# ProPrj_agronet_2025-02-23.net
KiCad netlist of a schematic drawn in EasyEDA Pro
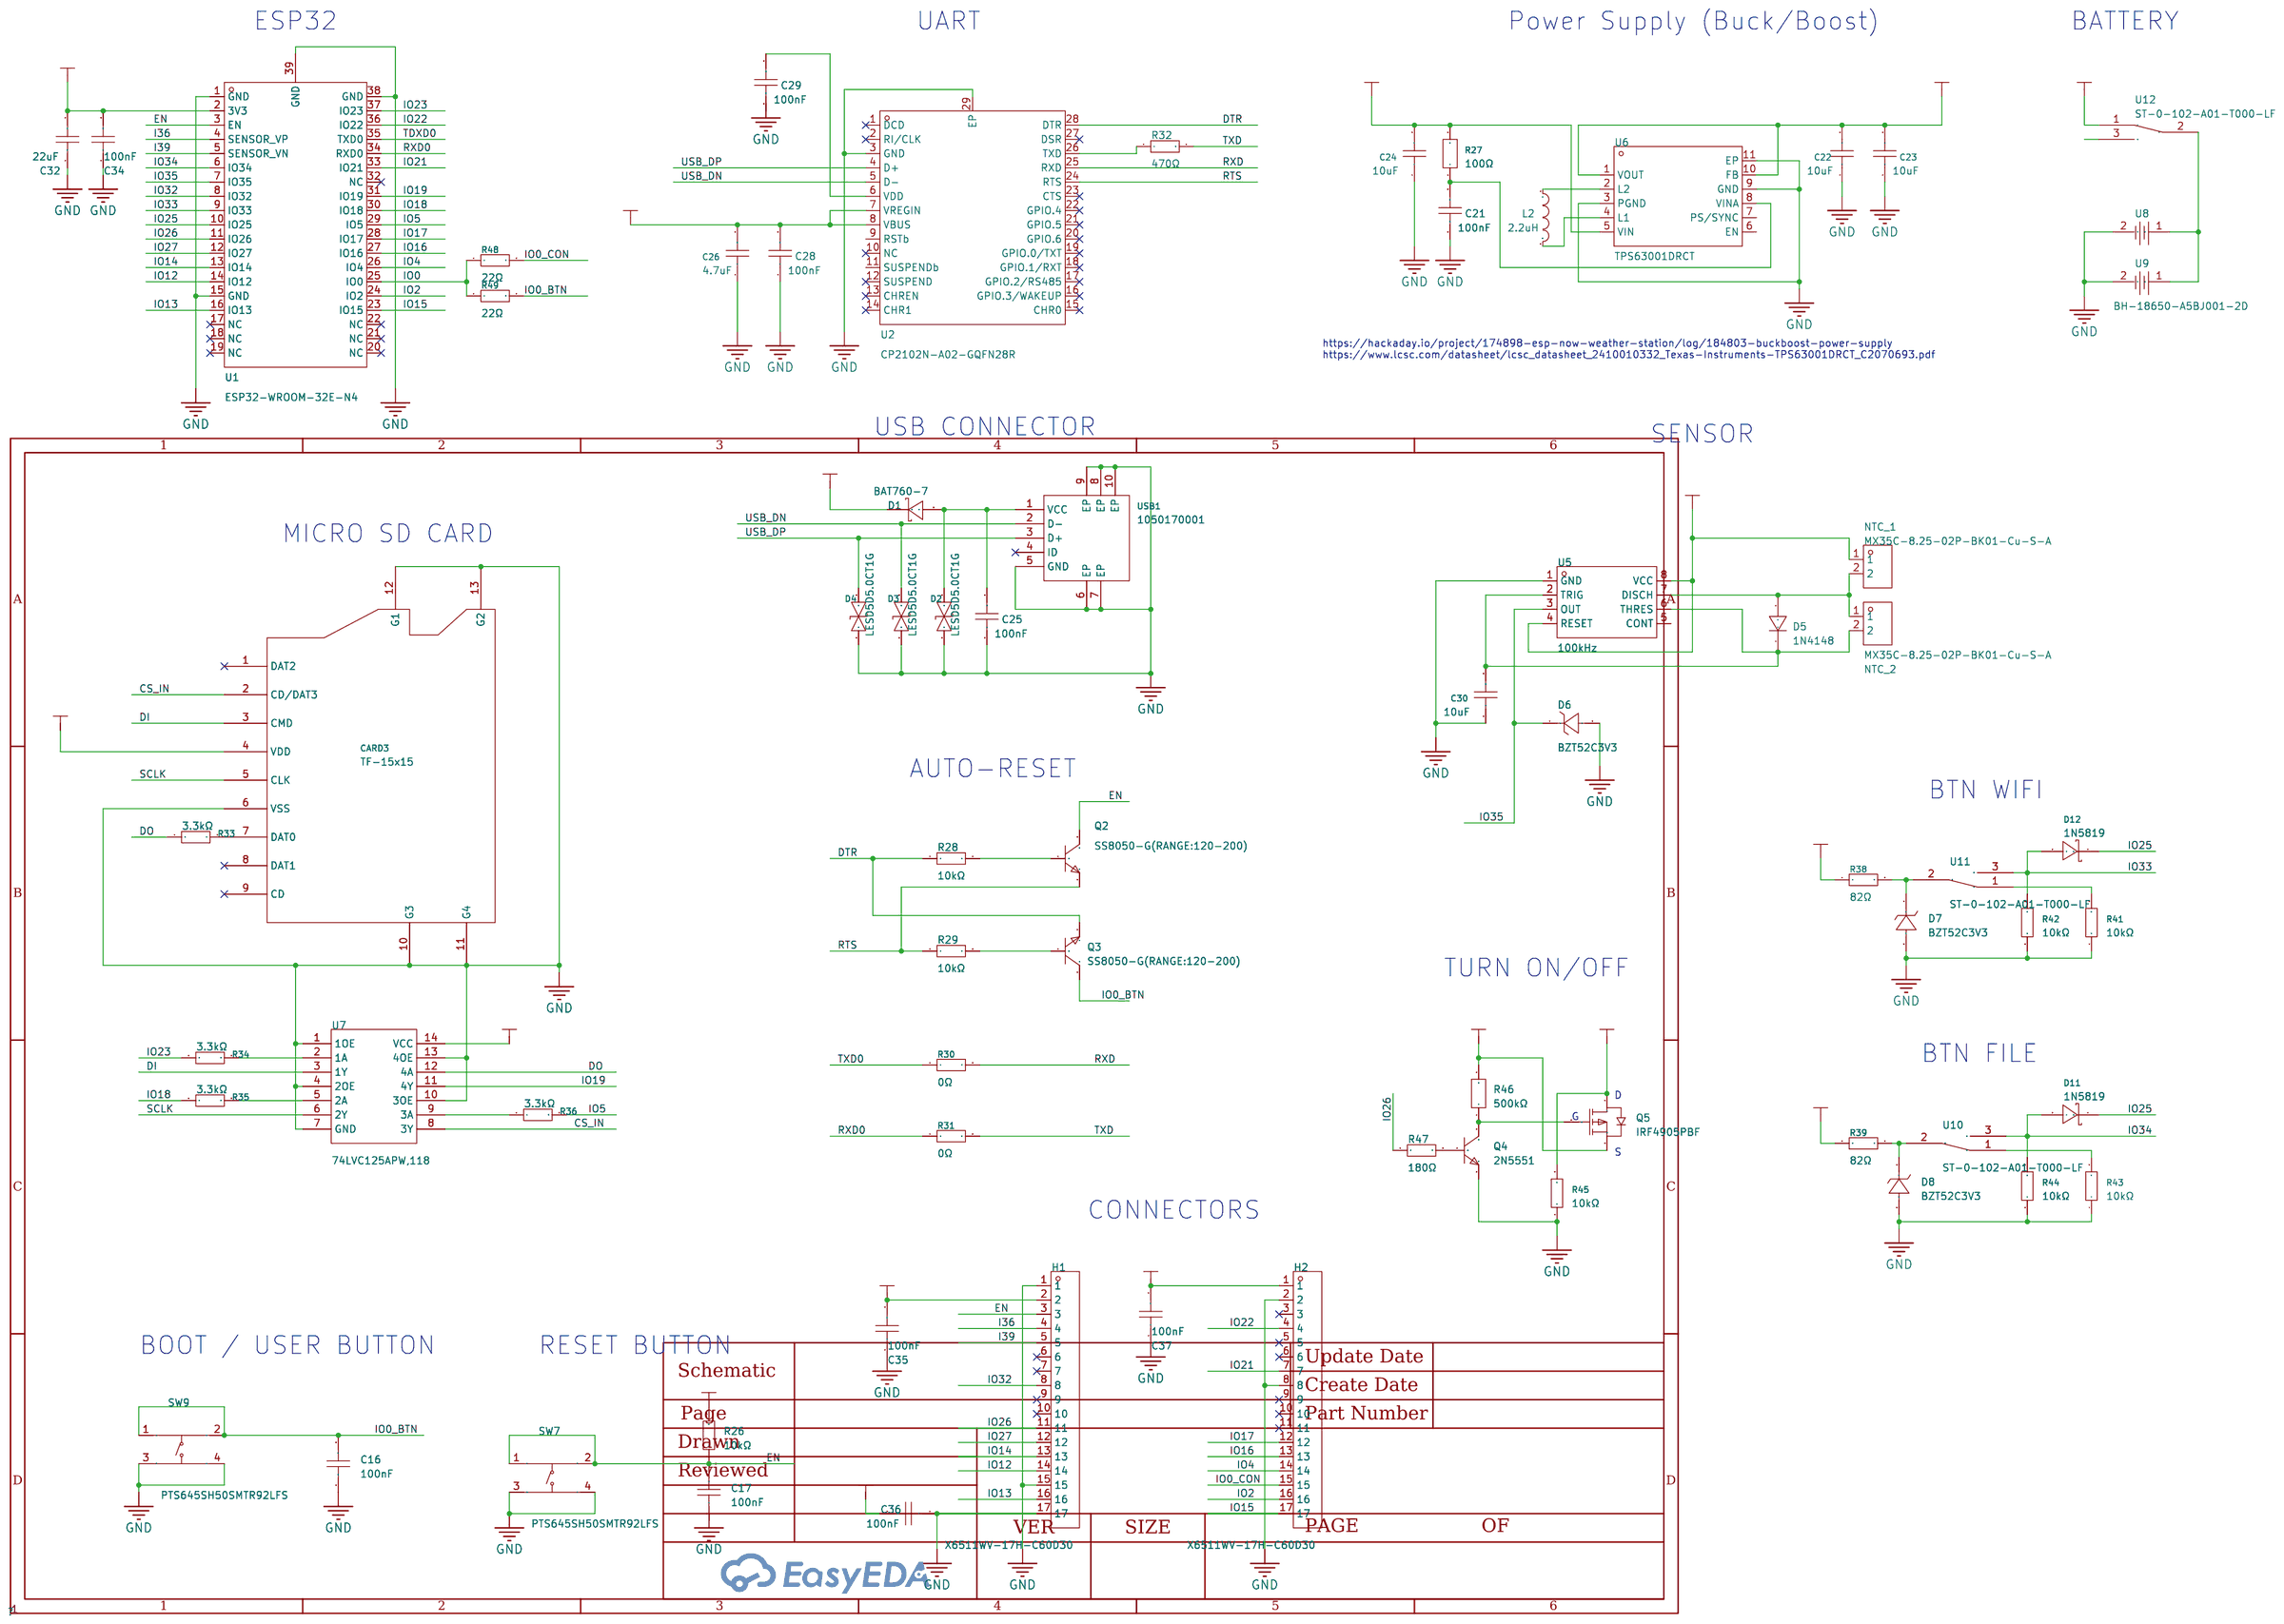
[diagram p0: schematic sheet]

(export (version "E")
  (design (tool "Eeschema 10.0.6"))
  (components
    (comp (ref "C16")
      (value "100nF")
      (footprint "easyedapro:C0402")
      (fields
        (field (name "Manufacturer Part") "CL05B104KO5NNNC")
        (field (name "Manufacturer") "SAMSUNG(三星)")
      )
      (libsource (lib "easyedapro") (part "CL05B104KO5NNNC"))
    )
    (comp (ref "C17")
      (value "100nF")
      (footprint "easyedapro:C0402")
      (fields
        (field (name "Manufacturer Part") "CL05B104KO5NNNC")
        (field (name "Manufacturer") "SAMSUNG(三星)")
      )
      (libsource (lib "easyedapro") (part "CL05B104KO5NNNC"))
    )
    (comp (ref "C21")
      (value "100nF")
      (footprint "easyedapro:C0402")
      (fields
        (field (name "Manufacturer Part") "CL05B104KO5NNNC")
        (field (name "Manufacturer") "SAMSUNG(三星)")
      )
      (libsource (lib "easyedapro") (part "CL05B104KO5NNNC"))
    )
    (comp (ref "C22")
      (value "10uF")
      (footprint "easyedapro:C0603")
      (fields
        (field (name "Manufacturer Part") "CL10A106MQ8NNNC")
        (field (name "Manufacturer") "SAMSUNG(三星)")
      )
      (libsource (lib "easyedapro") (part "CL10A106MQ8NNNC"))
    )
    (comp (ref "C23")
      (value "10uF")
      (footprint "easyedapro:C0603")
      (fields
        (field (name "Manufacturer Part") "CL10A106MQ8NNNC")
        (field (name "Manufacturer") "SAMSUNG(三星)")
      )
      (libsource (lib "easyedapro") (part "CL10A106MQ8NNNC"))
    )
    (comp (ref "C24")
      (value "10uF")
      (footprint "easyedapro:C0603")
      (fields
        (field (name "Manufacturer Part") "CL10A106MQ8NNNC")
        (field (name "Manufacturer") "SAMSUNG(三星)")
      )
      (libsource (lib "easyedapro") (part "CL10A106MQ8NNNC"))
    )
    (comp (ref "C25")
      (value "100nF")
      (footprint "easyedapro:C0402")
      (fields
        (field (name "Manufacturer Part") "CL05B104KO5NNNC")
        (field (name "Manufacturer") "SAMSUNG(三星)")
      )
      (libsource (lib "easyedapro") (part "CL05B104KO5NNNC"))
    )
    (comp (ref "C26")
      (value "4.7uF")
      (footprint "easyedapro:C0402")
      (fields
        (field (name "Manufacturer Part") "CL05A475KP5NRNC")
        (field (name "Manufacturer") "SAMSUNG(三星)")
      )
      (libsource (lib "easyedapro") (part "CL05A475KP5NRNC"))
    )
    (comp (ref "C28")
      (value "100nF")
      (footprint "easyedapro:C0402")
      (fields
        (field (name "Manufacturer Part") "CL05B104KO5NNNC")
        (field (name "Manufacturer") "SAMSUNG(三星)")
      )
      (libsource (lib "easyedapro") (part "CL05B104KO5NNNC"))
    )
    (comp (ref "C29")
      (value "100nF")
      (footprint "easyedapro:C0402")
      (fields
        (field (name "Manufacturer Part") "CL05B104KO5NNNC")
        (field (name "Manufacturer") "SAMSUNG(三星)")
      )
      (libsource (lib "easyedapro") (part "CL05B104KO5NNNC"))
    )
    (comp (ref "C30")
      (value "10uF")
      (footprint "easyedapro:C0603")
      (fields
        (field (name "Manufacturer Part") "CL10A106MQ8NNNC")
        (field (name "Manufacturer") "SAMSUNG(三星)")
      )
      (libsource (lib "easyedapro") (part "CL10A106MQ8NNNC"))
    )
    (comp (ref "C32")
      (value "22uF")
      (footprint "easyedapro:C0805")
      (fields
        (field (name "Manufacturer Part") "CL21A226MAYNNNE")
        (field (name "Manufacturer") "SAMSUNG(三星)")
      )
      (libsource (lib "easyedapro") (part "CL21A226MAYNNNE"))
    )
    (comp (ref "C34")
      (value "100nF")
      (footprint "easyedapro:C0402")
      (fields
        (field (name "Manufacturer Part") "CL05B104KO5NNNC")
        (field (name "Manufacturer") "SAMSUNG(三星)")
      )
      (libsource (lib "easyedapro") (part "CL05B104KO5NNNC"))
    )
    (comp (ref "C35")
      (value "100nF")
      (footprint "easyedapro:C0402")
      (fields
        (field (name "Manufacturer Part") "CL05B104KO5NNNC")
        (field (name "Manufacturer") "SAMSUNG(三星)")
      )
      (libsource (lib "easyedapro") (part "CL05B104KO5NNNC"))
    )
    (comp (ref "C36")
      (value "100nF")
      (footprint "easyedapro:C0402")
      (fields
        (field (name "Manufacturer Part") "CL05B104KO5NNNC")
        (field (name "Manufacturer") "SAMSUNG(三星)")
      )
      (libsource (lib "easyedapro") (part "CL05B104KO5NNNC"))
    )
    (comp (ref "C37")
      (value "100nF")
      (footprint "easyedapro:C0402")
      (fields
        (field (name "Manufacturer Part") "CL05B104KO5NNNC")
        (field (name "Manufacturer") "SAMSUNG(三星)")
      )
      (libsource (lib "easyedapro") (part "CL05B104KO5NNNC"))
    )
    (comp (ref "CARD3")
      (value "TF-15x15")
      (footprint "easyedapro:TF-SMD_TF-15-15")
      (fields (field (name "Manufacturer") "SOFNG(硕方)"))
      (libsource (lib "easyedapro") (part "TF-15×15"))
    )
    (comp (ref "D1")
      (value "BAT760-7")
      (footprint "easyedapro:SOD-323_L1.8-W1.3-LS2.5-RD")
      (fields (field (name "Manufacturer") "DIODES(美台)"))
      (libsource (lib "easyedapro") (part "BAT760-7"))
    )
    (comp (ref "D2")
      (value "LESD5D5.0CT1G")
      (footprint "easyedapro:SOD-523_L1.2-W0.8-LS1.6-BI")
      (fields (field (name "Manufacturer") "LRC(乐山无线电)"))
      (libsource (lib "easyedapro") (part "LESD5D5.0CT1G"))
    )
    (comp (ref "D3")
      (value "LESD5D5.0CT1G")
      (footprint "easyedapro:SOD-523_L1.2-W0.8-LS1.6-BI")
      (fields (field (name "Manufacturer") "LRC(乐山无线电)"))
      (libsource (lib "easyedapro") (part "LESD5D5.0CT1G"))
    )
    (comp (ref "D4")
      (value "LESD5D5.0CT1G")
      (footprint "easyedapro:SOD-523_L1.2-W0.8-LS1.6-BI")
      (fields (field (name "Manufacturer") "LRC(乐山无线电)"))
      (libsource (lib "easyedapro") (part "LESD5D5.0CT1G"))
    )
    (comp (ref "D5")
      (value "1N4148")
      (footprint "easyedapro:DO-35_BD2.0-L4.0-P8.0-D0.5-RD")
      (libsource (lib "easyedapro") (part "1N4148_C13769"))
    )
    (comp (ref "D6")
      (value "BZT52C3V3")
      (footprint "easyedapro:SOD-123_L2.7-W1.6-LS3.7-RD")
      (description "Zener Voltage (Nom):3.3V Power Dissipation:350mW")
      (fields (field (name "Manufacturer") "XZT(信展通)"))
      (libsource (lib "easyedapro") (part "BZT52C3V3_C5805693"))
    )
    (comp (ref "D7")
      (value "BZT52C3V3")
      (footprint "easyedapro:SOD-123_L2.7-W1.6-LS3.7-RD")
      (description "Zener Voltage (Nom):3.3V Power Dissipation:350mW")
      (fields (field (name "Manufacturer") "XZT(信展通)"))
      (libsource (lib "easyedapro") (part "BZT52C3V3_C5805693"))
    )
    (comp (ref "D8")
      (value "BZT52C3V3")
      (footprint "easyedapro:SOD-123_L2.7-W1.6-LS3.7-RD")
      (description "Zener Voltage (Nom):3.3V Power Dissipation:350mW")
      (fields (field (name "Manufacturer") "XZT(信展通)"))
      (libsource (lib "easyedapro") (part "BZT52C3V3_C5805693"))
    )
    (comp (ref "D11")
      (value "1N5819")
      (footprint "easyedapro:DO-41_BD2.4-L4.7-P8.70-D0.9-RD")
      (description "Forward Voltage (Vf@If):600mV@1A Reverse Voltage (Vr):40V Average Rectified Current (Io):1A")
      (fields (field (name "Manufacturer") "星海"))
      (libsource (lib "easyedapro") (part "1N5819_C84620"))
    )
    (comp (ref "D12")
      (value "1N5819")
      (footprint "easyedapro:DO-41_BD2.4-L4.7-P8.70-D0.9-RD")
      (description "Forward Voltage (Vf@If):600mV@1A Reverse Voltage (Vr):40V Average Rectified Current (Io):1A")
      (fields (field (name "Manufacturer") "星海"))
      (libsource (lib "easyedapro") (part "1N5819_C84620"))
    )
    (comp (ref "H1")
      (value "X6511WV-17H-C60D30")
      (footprint "easyedapro:HDR-TH_17P-P2.54-V-M")
      (fields (field (name "Manufacturer") "XKB Connection(中国星坤)"))
      (libsource (lib "easyedapro") (part "X6511WV-17H-C30D60"))
    )
    (comp (ref "H2")
      (value "X6511WV-17H-C60D30")
      (footprint "easyedapro:HDR-TH_17P-P2.54-V-M")
      (fields (field (name "Manufacturer") "XKB Connection(中国星坤)"))
      (libsource (lib "easyedapro") (part "X6511WV-17H-C30D60"))
    )
    (comp (ref "L2")
      (value "2.2uH")
      (footprint "easyedapro:L1008")
      (fields (field (name "Manufacturer Part") "LQM2HPN2R2MG0L") (field (name "Manufacturer") "muRata(村田)"))
      (libsource (lib "easyedapro") (part "LQM2HPN2R2MG0L"))
    )
    (comp (ref "NTC_1")
      (value "MX35C-8.25-02P-BK01-Cu-S-A")
      (footprint "easyedapro:CONN-TH_MX35C-8.25-02P-BK01-CU-S-A")
      (fields (field (name "Manufacturer") "MAX(迈旭)"))
      (libsource (lib "easyedapro") (part "MX35C-8.25-02P-BK01-CU-S-A"))
    )
    (comp (ref "NTC_2")
      (value "MX35C-8.25-02P-BK01-Cu-S-A")
      (footprint "easyedapro:CONN-TH_MX35C-8.25-02P-BK01-CU-S-A")
      (fields (field (name "Manufacturer") "MAX(迈旭)"))
      (libsource (lib "easyedapro") (part "MX35C-8.25-02P-BK01-CU-S-A"))
    )
    (comp (ref "Q2")
      (value "SS8050-G(RANGE:120-200)")
      (footprint "easyedapro:SOT-23-3_L2.9-W1.3-P1.90-LS2.4-BR")
      (fields (field (name "Manufacturer") "CJ(江苏长电/长晶)"))
      (libsource (lib "easyedapro") (part "SS8050-G"))
    )
    (comp (ref "Q3")
      (value "SS8050-G(RANGE:120-200)")
      (footprint "easyedapro:SOT-23-3_L2.9-W1.3-P1.90-LS2.4-BR")
      (fields (field (name "Manufacturer") "CJ(江苏长电/长晶)"))
      (libsource (lib "easyedapro") (part "SS8050-G"))
    )
    (comp (ref "Q4")
      (value "2N5551")
      (footprint "easyedapro:TO-92-3_L4.5-W3.5-P1.27-L")
      (fields (field (name "Manufacturer") "Slkor(萨科微)"))
      (libsource (lib "easyedapro") (part "2N5551_C2936034"))
    )
    (comp (ref "Q5")
      (value "IRF4905PBF")
      (footprint "easyedapro:TO-220-3_L10.0-W4.5-P2.54-T")
      (fields (field (name "Manufacturer") "Infineon(英飞凌)"))
      (libsource (lib "easyedapro") (part "IRF4905PBF"))
    )
    (comp (ref "R26")
      (value "10kΩ")
      (footprint "easyedapro:R0402")
      (fields
        (field (name "Manufacturer Part") "0402WGF1002TCE")
        (field (name "Manufacturer") "UNI-ROYAL(厚声)")
      )
      (libsource (lib "easyedapro") (part "0402WGF1002TCE"))
    )
    (comp (ref "R27")
      (value "100Ω")
      (footprint "easyedapro:R0402")
      (fields
        (field (name "Manufacturer Part") "TC0250B1000TCC")
        (field (name "Manufacturer") "UNI-ROYAL(厚声)")
      )
      (libsource (lib "easyedapro") (part "TC0250B1000TCC"))
    )
    (comp (ref "R28")
      (value "10kΩ")
      (footprint "easyedapro:R0402")
      (fields
        (field (name "Manufacturer Part") "0402WGF1002TCE")
        (field (name "Manufacturer") "UNI-ROYAL(厚声)")
      )
      (libsource (lib "easyedapro") (part "0402WGF1002TCE"))
    )
    (comp (ref "R29")
      (value "10kΩ")
      (footprint "easyedapro:R0402")
      (fields
        (field (name "Manufacturer Part") "0402WGF1002TCE")
        (field (name "Manufacturer") "UNI-ROYAL(厚声)")
      )
      (libsource (lib "easyedapro") (part "0402WGF1002TCE"))
    )
    (comp (ref "R30")
      (value "0Ω")
      (footprint "easyedapro:R0402")
      (fields
        (field (name "Manufacturer Part") "0402WGF0000TCE")
        (field (name "Manufacturer") "UNI-ROYAL(厚声)")
      )
      (libsource (lib "easyedapro") (part "0402WGF0000TCE"))
    )
    (comp (ref "R31")
      (value "0Ω")
      (footprint "easyedapro:R0402")
      (fields
        (field (name "Manufacturer Part") "0402WGF0000TCE")
        (field (name "Manufacturer") "UNI-ROYAL(厚声)")
      )
      (libsource (lib "easyedapro") (part "0402WGF0000TCE"))
    )
    (comp (ref "R32")
      (value "470Ω")
      (footprint "easyedapro:R0603")
      (fields
        (field (name "Manufacturer Part") "0603WAF4700T5E")
        (field (name "Manufacturer") "UNI-ROYAL(厚声)")
      )
      (libsource (lib "easyedapro") (part "0603WAF4700T5E"))
    )
    (comp (ref "R33")
      (value "3.3kΩ")
      (footprint "easyedapro:R0402")
      (fields
        (field (name "Manufacturer Part") "0402WGF3301TCE")
        (field (name "Manufacturer") "UNI-ROYAL(厚声)")
      )
      (libsource (lib "easyedapro") (part "0402WGF3301TCE"))
    )
    (comp (ref "R34")
      (value "3.3kΩ")
      (footprint "easyedapro:R0402")
      (fields
        (field (name "Manufacturer Part") "0402WGF3301TCE")
        (field (name "Manufacturer") "UNI-ROYAL(厚声)")
      )
      (libsource (lib "easyedapro") (part "0402WGF3301TCE"))
    )
    (comp (ref "R35")
      (value "3.3kΩ")
      (footprint "easyedapro:R0402")
      (fields
        (field (name "Manufacturer Part") "0402WGF3301TCE")
        (field (name "Manufacturer") "UNI-ROYAL(厚声)")
      )
      (libsource (lib "easyedapro") (part "0402WGF3301TCE"))
    )
    (comp (ref "R36")
      (value "3.3kΩ")
      (footprint "easyedapro:R0402")
      (fields
        (field (name "Manufacturer Part") "0402WGF3301TCE")
        (field (name "Manufacturer") "UNI-ROYAL(厚声)")
      )
      (libsource (lib "easyedapro") (part "0402WGF3301TCE"))
    )
    (comp (ref "R38")
      (value "82Ω")
      (footprint "easyedapro:R0402")
      (fields
        (field (name "Manufacturer Part") "0402WGF820JTCE")
        (field (name "Manufacturer") "UNI-ROYAL(厚声)")
      )
      (libsource (lib "easyedapro") (part "0402WGF820JTCE"))
    )
    (comp (ref "R39")
      (value "82Ω")
      (footprint "easyedapro:R0402")
      (fields
        (field (name "Manufacturer Part") "0402WGF820JTCE")
        (field (name "Manufacturer") "UNI-ROYAL(厚声)")
      )
      (libsource (lib "easyedapro") (part "0402WGF820JTCE"))
    )
    (comp (ref "R41")
      (value "10kΩ")
      (footprint "easyedapro:R0805")
      (fields
        (field (name "Manufacturer Part") "0805W8F1002T5E")
        (field (name "Manufacturer") "UNI-ROYAL(厚声)")
      )
      (libsource (lib "easyedapro") (part "0805W8F1002T5E"))
    )
    (comp (ref "R42")
      (value "10kΩ")
      (footprint "easyedapro:R0805")
      (fields
        (field (name "Manufacturer Part") "0805W8F1002T5E")
        (field (name "Manufacturer") "UNI-ROYAL(厚声)")
      )
      (libsource (lib "easyedapro") (part "0805W8F1002T5E"))
    )
    (comp (ref "R43")
      (value "10kΩ")
      (footprint "easyedapro:R0805")
      (fields
        (field (name "Manufacturer Part") "0805W8F1002T5E")
        (field (name "Manufacturer") "UNI-ROYAL(厚声)")
      )
      (libsource (lib "easyedapro") (part "0805W8F1002T5E"))
    )
    (comp (ref "R44")
      (value "10kΩ")
      (footprint "easyedapro:R0805")
      (fields
        (field (name "Manufacturer Part") "0805W8F1002T5E")
        (field (name "Manufacturer") "UNI-ROYAL(厚声)")
      )
      (libsource (lib "easyedapro") (part "0805W8F1002T5E"))
    )
    (comp (ref "R45")
      (value "10kΩ")
      (footprint "easyedapro:R0805")
      (fields
        (field (name "Manufacturer Part") "0805W8F1002T5E")
        (field (name "Manufacturer") "UNI-ROYAL(厚声)")
      )
      (libsource (lib "easyedapro") (part "0805W8F1002T5E"))
    )
    (comp (ref "R46")
      (value "500kΩ")
      (footprint "easyedapro:R0603")
      (fields (field (name "Manufacturer Part") "AR03BTCX5003N") (field (name "Manufacturer") "Viking(光颉)"))
      (libsource (lib "easyedapro") (part "AR03BTCX5003N"))
    )
    (comp (ref "R47")
      (value "180Ω")
      (footprint "easyedapro:R0603")
      (fields
        (field (name "Manufacturer Part") "0603WAF1800T5E")
        (field (name "Manufacturer") "UNI-ROYAL(厚声)")
      )
      (libsource (lib "easyedapro") (part "0603WAF1800T5E"))
    )
    (comp (ref "R48")
      (value "22Ω")
      (footprint "easyedapro:R0402")
      (fields
        (field (name "Manufacturer Part") "0402WGF220JTCE")
        (field (name "Manufacturer") "UNI-ROYAL(厚声)")
      )
      (libsource (lib "easyedapro") (part "0402WGF220JTCE"))
    )
    (comp (ref "R49")
      (value "22Ω")
      (footprint "easyedapro:R0402")
      (fields
        (field (name "Manufacturer Part") "0402WGF220JTCE")
        (field (name "Manufacturer") "UNI-ROYAL(厚声)")
      )
      (libsource (lib "easyedapro") (part "0402WGF220JTCE"))
    )
    (comp (ref "SW7")
      (value "PTS645SH50SMTR92LFS")
      (footprint "easyedapro:KEY-SMD_4P-L6.0-W6.0-P4.50-LS9.0")
      (fields (field (name "Manufacturer") "C&K"))
      (libsource (lib "easyedapro") (part "PTS645SH50SMTR92LFS"))
    )
    (comp (ref "SW9")
      (value "PTS645SH50SMTR92LFS")
      (footprint "easyedapro:KEY-SMD_4P-L6.0-W6.0-P4.50-LS9.0")
      (fields (field (name "Manufacturer") "C&K"))
      (libsource (lib "easyedapro") (part "PTS645SH50SMTR92LFS"))
    )
    (comp (ref "U1")
      (value "ESP32-WROOM-32E-N4")
      (footprint "easyedapro:WIFI-SMD_ESP32-WROOM-32E")
      (fields (field (name "Manufacturer") "ESPRESSIF(乐鑫)"))
      (libsource (lib "easyedapro") (part "ESP32-WROOM-32E(4MB)"))
    )
    (comp (ref "U2")
      (value "CP2102N-A02-GQFN28R")
      (footprint "easyedapro:QFN-28_L5.0-W5.0-P0.50-TL-EP3.3")
      (fields (field (name "Manufacturer") "SKYWORKS/SILICON LABS(芯科)"))
      (libsource (lib "easyedapro") (part "CP2102N-A02-GQFN28R"))
    )
    (comp (ref "U5")
      (value "100kHz")
      (footprint "easyedapro:DIP-8_L9.8-W6.6-P2.54-LS7.6-BL")
      (fields (field (name "Manufacturer Part") "NE555P") (field (name "Manufacturer") "TI(德州仪器)"))
      (libsource (lib "easyedapro") (part "NE555P"))
    )
    (comp (ref "U6")
      (value "TPS63001DRCT")
      (footprint "easyedapro:VSON-10_L3.0-W3.0-P0.50-TL-EP")
      (fields (field (name "Manufacturer") "TI(德州仪器)"))
      (libsource (lib "easyedapro") (part "TPS63001DRCT"))
    )
    (comp (ref "U7")
      (value "74LVC125APW,118")
      (footprint "easyedapro:TSSOP-14_L5.0-W4.4-P0.65-LS6.4-BL")
      (fields (field (name "Manufacturer") "Nexperia(安世)"))
      (libsource (lib "easyedapro") (part "74LVC125APW,118"))
    )
    (comp (ref "U8")
      (value "BH-18650-A5BJ001-2D")
      (footprint "easyedapro:BAT-TH_BH-18650-A5BJ001-2D")
      (fields (field (name "Manufacturer") "MYOUNG(美阳)"))
      (libsource (lib "easyedapro") (part "BH-18650-A5BJ001-2D"))
    )
    (comp (ref "U9")
      (value "BH-18650-A5BJ001-2D")
      (footprint "easyedapro:BAT-TH_BH-18650-A5BJ001-2D")
      (fields (field (name "Manufacturer") "MYOUNG(美阳)"))
      (libsource (lib "easyedapro") (part "BH-18650-A5BJ001-2D"))
    )
    (comp (ref "U10")
      (value "ST-0-102-A01-T000-LF")
      (footprint "easyedapro:SW-TH_3P-L8.3-W5.2-P2.54_ST-0-102-A01-T000")
      (fields (field (name "Manufacturer") "YUEN FUNG(源丰)"))
      (libsource (lib "easyedapro") (part "ST-0-102-A01-T000-LF+PJ"))
    )
    (comp (ref "U11")
      (value "ST-0-102-A01-T000-LF")
      (footprint "easyedapro:SW-TH_3P-L8.3-W5.2-P2.54_ST-0-102-A01-T000")
      (fields (field (name "Manufacturer") "YUEN FUNG(源丰)"))
      (libsource (lib "easyedapro") (part "ST-0-102-A01-T000-LF+PJ"))
    )
    (comp (ref "U12")
      (value "ST-0-102-A01-T000-LF")
      (footprint "easyedapro:SW-TH_3P-L8.3-W5.2-P2.54_ST-0-102-A01-T000")
      (fields (field (name "Manufacturer") "YUEN FUNG(源丰)"))
      (libsource (lib "easyedapro") (part "ST-0-102-A01-T000-LF+PJ"))
    )
    (comp (ref "USB1")
      (value "1050170001")
      (footprint "easyedapro:MICRO-USB-SMD_105017-0001")
      (fields (field (name "Manufacturer") "MOLEX"))
      (libsource (lib "easyedapro") (part "105017-0001"))
    )
  )
  (nets
    (net (code "1") (name "/CS_IN") (class "Default")
      (node (ref "CARD3") (pin "2") (pinfunction "CD/DAT3_2") (pintype "input"))
      (node (ref "U7") (pin "8") (pinfunction "3Y_8") (pintype "input"))
    )
    (net (code "2") (name "/DI") (class "Default")
      (node (ref "CARD3") (pin "3") (pinfunction "CMD_3") (pintype "input"))
      (node (ref "U7") (pin "3") (pinfunction "1Y_3") (pintype "input"))
    )
    (net (code "3") (name "/DO") (class "Default")
      (node (ref "R33") (pin "1") (pinfunction "1_1") (pintype "input"))
      (node (ref "U7") (pin "12") (pinfunction "4A_12") (pintype "input"))
    )
    (net (code "4") (name "/DTR") (class "Default")
      (node (ref "Q3") (pin "2") (pinfunction "E_2") (pintype "input"))
      (node (ref "R28") (pin "1") (pinfunction "1_1") (pintype "input"))
      (node (ref "U2") (pin "28") (pinfunction "DTR_28") (pintype "unspecified"))
    )
    (net (code "5") (name "/EN") (class "Default")
      (node (ref "C17") (pin "2") (pinfunction "2_2") (pintype "unspecified"))
      (node (ref "H1") (pin "3") (pinfunction "3_3") (pintype "unspecified"))
      (node (ref "Q2") (pin "3") (pinfunction "C_3") (pintype "input"))
      (node (ref "R26") (pin "1") (pinfunction "1_1") (pintype "input"))
      (node (ref "SW7") (pin "1") (pinfunction "1_1") (pintype "unspecified"))
      (node (ref "SW7") (pin "2") (pinfunction "2_2") (pintype "unspecified"))
      (node (ref "U1") (pin "3") (pinfunction "EN_3") (pintype "unspecified"))
    )
    (net (code "6") (name "/I36") (class "Default")
      (node (ref "H1") (pin "4") (pinfunction "4_4") (pintype "unspecified"))
      (node (ref "U1") (pin "4") (pinfunction "SENSOR_VP_4") (pintype "unspecified"))
    )
    (net (code "7") (name "/I39") (class "Default")
      (node (ref "H1") (pin "5") (pinfunction "5_5") (pintype "unspecified"))
      (node (ref "U1") (pin "5") (pinfunction "SENSOR_VN_5") (pintype "unspecified"))
    )
    (net (code "8") (name "/IO0") (class "Default")
      (node (ref "R48") (pin "1") (pinfunction "1_1") (pintype "input"))
      (node (ref "R49") (pin "1") (pinfunction "1_1") (pintype "input"))
      (node (ref "U1") (pin "25") (pinfunction "IO0_25") (pintype "unspecified"))
    )
    (net (code "9") (name "/IO0_BTN") (class "Default")
      (node (ref "C16") (pin "2") (pinfunction "2_2") (pintype "unspecified"))
      (node (ref "Q3") (pin "3") (pinfunction "C_3") (pintype "input"))
      (node (ref "R49") (pin "2") (pinfunction "2_2") (pintype "input"))
      (node (ref "SW9") (pin "1") (pinfunction "1_1") (pintype "unspecified"))
      (node (ref "SW9") (pin "2") (pinfunction "2_2") (pintype "unspecified"))
    )
    (net (code "10") (name "/IO0_CON") (class "Default")
      (node (ref "H2") (pin "15") (pinfunction "15_15") (pintype "unspecified"))
      (node (ref "R48") (pin "2") (pinfunction "2_2") (pintype "input"))
    )
    (net (code "11") (name "/IO2") (class "Default")
      (node (ref "H2") (pin "16") (pinfunction "16_16") (pintype "unspecified"))
      (node (ref "U1") (pin "24") (pinfunction "IO2_24") (pintype "unspecified"))
    )
    (net (code "12") (name "/IO4") (class "Default")
      (node (ref "H2") (pin "14") (pinfunction "14_14") (pintype "unspecified"))
      (node (ref "U1") (pin "26") (pinfunction "IO4_26") (pintype "unspecified"))
    )
    (net (code "13") (name "/IO5") (class "Default")
      (node (ref "R36") (pin "2") (pinfunction "2_2") (pintype "input"))
      (node (ref "U1") (pin "29") (pinfunction "IO5_29") (pintype "unspecified"))
    )
    (net (code "14") (name "/IO12") (class "Default")
      (node (ref "H1") (pin "14") (pinfunction "14_14") (pintype "unspecified"))
      (node (ref "U1") (pin "14") (pinfunction "IO12_14") (pintype "unspecified"))
    )
    (net (code "15") (name "/IO13") (class "Default")
      (node (ref "H1") (pin "16") (pinfunction "16_16") (pintype "unspecified"))
      (node (ref "U1") (pin "16") (pinfunction "IO13_16") (pintype "unspecified"))
    )
    (net (code "16") (name "/IO14") (class "Default")
      (node (ref "H1") (pin "13") (pinfunction "13_13") (pintype "unspecified"))
      (node (ref "U1") (pin "13") (pinfunction "IO14_13") (pintype "unspecified"))
    )
    (net (code "17") (name "/IO15") (class "Default")
      (node (ref "H2") (pin "17") (pinfunction "17_17") (pintype "unspecified"))
      (node (ref "U1") (pin "23") (pinfunction "IO15_23") (pintype "unspecified"))
    )
    (net (code "18") (name "/IO16") (class "Default")
      (node (ref "H2") (pin "13") (pinfunction "13_13") (pintype "unspecified"))
      (node (ref "U1") (pin "27") (pinfunction "IO16_27") (pintype "unspecified"))
    )
    (net (code "19") (name "/IO17") (class "Default")
      (node (ref "H2") (pin "12") (pinfunction "12_12") (pintype "unspecified"))
      (node (ref "U1") (pin "28") (pinfunction "IO17_28") (pintype "unspecified"))
    )
    (net (code "20") (name "/IO18") (class "Default")
      (node (ref "R35") (pin "1") (pinfunction "1_1") (pintype "input"))
      (node (ref "U1") (pin "30") (pinfunction "IO18_30") (pintype "unspecified"))
    )
    (net (code "21") (name "/IO19") (class "Default")
      (node (ref "U1") (pin "31") (pinfunction "IO19_31") (pintype "unspecified"))
      (node (ref "U7") (pin "11") (pinfunction "4Y_11") (pintype "input"))
    )
    (net (code "22") (name "/IO21") (class "Default")
      (node (ref "H2") (pin "7") (pinfunction "7_7") (pintype "unspecified"))
      (node (ref "U1") (pin "33") (pinfunction "IO21_33") (pintype "unspecified"))
    )
    (net (code "23") (name "/IO22") (class "Default")
      (node (ref "H2") (pin "4") (pinfunction "4_4") (pintype "unspecified"))
      (node (ref "U1") (pin "36") (pinfunction "IO22_36") (pintype "unspecified"))
    )
    (net (code "24") (name "/IO23") (class "Default")
      (node (ref "R34") (pin "1") (pinfunction "1_1") (pintype "input"))
      (node (ref "U1") (pin "37") (pinfunction "IO23_37") (pintype "unspecified"))
    )
    (net (code "25") (name "/IO25") (class "Default")
      (node (ref "D11") (pin "1") (pinfunction "C_1") (pintype "input"))
      (node (ref "D12") (pin "1") (pinfunction "C_1") (pintype "input"))
      (node (ref "U1") (pin "10") (pinfunction "IO25_10") (pintype "unspecified"))
    )
    (net (code "26") (name "/IO26") (class "Default")
      (node (ref "H1") (pin "11") (pinfunction "11_11") (pintype "unspecified"))
      (node (ref "R47") (pin "1") (pinfunction "1_1") (pintype "input"))
      (node (ref "U1") (pin "11") (pinfunction "IO26_11") (pintype "unspecified"))
    )
    (net (code "27") (name "/IO27") (class "Default")
      (node (ref "H1") (pin "12") (pinfunction "12_12") (pintype "unspecified"))
      (node (ref "U1") (pin "12") (pinfunction "IO27_12") (pintype "unspecified"))
    )
    (net (code "28") (name "/IO32") (class "Default")
      (node (ref "H1") (pin "8") (pinfunction "8_8") (pintype "unspecified"))
      (node (ref "U1") (pin "8") (pinfunction "IO32_8") (pintype "unspecified"))
    )
    (net (code "29") (name "/IO33") (class "Default")
      (node (ref "D12") (pin "2") (pinfunction "A_2") (pintype "input"))
      (node (ref "R42") (pin "2") (pinfunction "2_2") (pintype "input"))
      (node (ref "U1") (pin "9") (pinfunction "IO33_9") (pintype "unspecified"))
      (node (ref "U11") (pin "3") (pinfunction "3_3") (pintype "unspecified"))
    )
    (net (code "30") (name "/IO34") (class "Default")
      (node (ref "D11") (pin "2") (pinfunction "A_2") (pintype "input"))
      (node (ref "R44") (pin "2") (pinfunction "2_2") (pintype "input"))
      (node (ref "U1") (pin "6") (pinfunction "IO34_6") (pintype "unspecified"))
      (node (ref "U10") (pin "3") (pinfunction "3_3") (pintype "unspecified"))
    )
    (net (code "31") (name "/IO35") (class "Default")
      (node (ref "D6") (pin "1") (pinfunction "K_1") (pintype "unspecified"))
      (node (ref "U1") (pin "7") (pinfunction "IO35_7") (pintype "unspecified"))
      (node (ref "U5") (pin "3") (pinfunction "OUT_3") (pintype "input"))
    )
    (net (code "32") (name "/RTS") (class "Default")
      (node (ref "Q2") (pin "2") (pinfunction "E_2") (pintype "input"))
      (node (ref "R29") (pin "1") (pinfunction "1_1") (pintype "input"))
      (node (ref "U2") (pin "24") (pinfunction "RTS_24") (pintype "unspecified"))
    )
    (net (code "33") (name "/RXD") (class "Default")
      (node (ref "R30") (pin "2") (pinfunction "2_2") (pintype "input"))
      (node (ref "U2") (pin "25") (pinfunction "RXD_25") (pintype "unspecified"))
    )
    (net (code "34") (name "/RXD0") (class "Default")
      (node (ref "R31") (pin "1") (pinfunction "1_1") (pintype "input"))
      (node (ref "U1") (pin "34") (pinfunction "RXD0_34") (pintype "unspecified"))
    )
    (net (code "35") (name "/SCLK") (class "Default")
      (node (ref "CARD3") (pin "5") (pinfunction "CLK_5") (pintype "input"))
      (node (ref "U7") (pin "6") (pinfunction "2Y_6") (pintype "input"))
    )
    (net (code "36") (name "/TDXD0") (class "Default")
      (node (ref "U1") (pin "35") (pinfunction "TXD0_35") (pintype "unspecified"))
    )
    (net (code "37") (name "/TXD") (class "Default")
      (node (ref "R31") (pin "2") (pinfunction "2_2") (pintype "input"))
      (node (ref "R32") (pin "2") (pinfunction "2_2") (pintype "input"))
    )
    (net (code "38") (name "/TXD0") (class "Default")
      (node (ref "R30") (pin "1") (pinfunction "1_1") (pintype "input"))
    )
    (net (code "39") (name "/USB_DN") (class "Default")
      (node (ref "D3") (pin "2") (pinfunction "2_2") (pintype "input"))
      (node (ref "U2") (pin "5") (pinfunction "D-_5") (pintype "unspecified"))
      (node (ref "USB1") (pin "2") (pinfunction "D-_2") (pintype "input"))
    )
    (net (code "40") (name "/USB_DP") (class "Default")
      (node (ref "D4") (pin "2") (pinfunction "2_2") (pintype "input"))
      (node (ref "U2") (pin "4") (pinfunction "D+_4") (pintype "unspecified"))
      (node (ref "USB1") (pin "3") (pinfunction "D+_3") (pintype "input"))
    )
    (net (code "41") (name "3V3") (class "Default")
      (node (ref "C22") (pin "2") (pinfunction "2_2") (pintype "input"))
      (node (ref "C23") (pin "2") (pinfunction "2_2") (pintype "input"))
      (node (ref "C32") (pin "2") (pinfunction "2_2") (pintype "unspecified"))
      (node (ref "C34") (pin "2") (pinfunction "2_2") (pintype "unspecified"))
      (node (ref "C35") (pin "2") (pinfunction "2_2") (pintype "unspecified"))
      (node (ref "C37") (pin "2") (pinfunction "2_2") (pintype "unspecified"))
      (node (ref "CARD3") (pin "4") (pinfunction "VDD_4") (pintype "input"))
      (node (ref "H1") (pin "2") (pinfunction "2_2") (pintype "unspecified"))
      (node (ref "H2") (pin "1") (pinfunction "1_1") (pintype "unspecified"))
      (node (ref "R26") (pin "2") (pinfunction "2_2") (pintype "input"))
      (node (ref "U1") (pin "2") (pinfunction "3V3_2") (pintype "unspecified"))
      (node (ref "U6") (pin "1") (pinfunction "VOUT_1") (pintype "unspecified"))
      (node (ref "U6") (pin "10") (pinfunction "FB_10") (pintype "unspecified"))
      (node (ref "U7") (pin "14") (pinfunction "VCC_14") (pintype "input"))
    )
    (net (code "42") (name "EXT_5V") (class "Default")
      (node (ref "C26") (pin "2") (pinfunction "2_2") (pintype "input"))
      (node (ref "C28") (pin "2") (pinfunction "2_2") (pintype "unspecified"))
      (node (ref "C36") (pin "2") (pinfunction "2_2") (pintype "unspecified"))
      (node (ref "D1") (pin "1") (pinfunction "1_1") (pintype "unspecified"))
      (node (ref "U2") (pin "7") (pinfunction "VREGIN_7") (pintype "unspecified"))
      (node (ref "U2") (pin "8") (pinfunction "VBUS_8") (pintype "unspecified"))
    )
    (net (code "43") (name "GND") (class "Default")
      (node (ref "C16") (pin "1") (pinfunction "1_1") (pintype "unspecified"))
      (node (ref "C17") (pin "1") (pinfunction "1_1") (pintype "unspecified"))
      (node (ref "C21") (pin "1") (pinfunction "1_1") (pintype "unspecified"))
      (node (ref "C22") (pin "1") (pinfunction "1_1") (pintype "input"))
      (node (ref "C23") (pin "1") (pinfunction "1_1") (pintype "input"))
      (node (ref "C24") (pin "1") (pinfunction "1_1") (pintype "input"))
      (node (ref "C25") (pin "1") (pinfunction "1_1") (pintype "unspecified"))
      (node (ref "C26") (pin "1") (pinfunction "1_1") (pintype "input"))
      (node (ref "C28") (pin "1") (pinfunction "1_1") (pintype "unspecified"))
      (node (ref "C29") (pin "1") (pinfunction "1_1") (pintype "unspecified"))
      (node (ref "C30") (pin "1") (pinfunction "1_1") (pintype "input"))
      (node (ref "C32") (pin "1") (pinfunction "1_1") (pintype "unspecified"))
      (node (ref "C34") (pin "1") (pinfunction "1_1") (pintype "unspecified"))
      (node (ref "C35") (pin "1") (pinfunction "1_1") (pintype "unspecified"))
      (node (ref "C36") (pin "1") (pinfunction "1_1") (pintype "unspecified"))
      (node (ref "C37") (pin "1") (pinfunction "1_1") (pintype "unspecified"))
      (node (ref "CARD3") (pin "10") (pinfunction "G3_10") (pintype "input"))
      (node (ref "CARD3") (pin "11") (pinfunction "G4_11") (pintype "input"))
      (node (ref "CARD3") (pin "12") (pinfunction "G1_12") (pintype "input"))
      (node (ref "CARD3") (pin "13") (pinfunction "G2_13") (pintype "input"))
      (node (ref "CARD3") (pin "6") (pinfunction "VSS_6") (pintype "input"))
      (node (ref "D2") (pin "1") (pinfunction "1_1") (pintype "input"))
      (node (ref "D3") (pin "1") (pinfunction "1_1") (pintype "input"))
      (node (ref "D4") (pin "1") (pinfunction "1_1") (pintype "input"))
      (node (ref "D6") (pin "2") (pinfunction "A_2") (pintype "unspecified"))
      (node (ref "D7") (pin "2") (pinfunction "A_2") (pintype "unspecified"))
      (node (ref "D8") (pin "2") (pinfunction "A_2") (pintype "unspecified"))
      (node (ref "H1") (pin "1") (pinfunction "1_1") (pintype "unspecified"))
      (node (ref "H1") (pin "15") (pinfunction "15_15") (pintype "unspecified"))
      (node (ref "H1") (pin "17") (pinfunction "17_17") (pintype "unspecified"))
      (node (ref "H2") (pin "2") (pinfunction "2_2") (pintype "unspecified"))
      (node (ref "H2") (pin "8") (pinfunction "8_8") (pintype "unspecified"))
      (node (ref "Q4") (pin "1") (pinfunction "E_1") (pintype "input"))
      (node (ref "R41") (pin "1") (pinfunction "1_1") (pintype "input"))
      (node (ref "R42") (pin "1") (pinfunction "1_1") (pintype "input"))
      (node (ref "R43") (pin "1") (pinfunction "1_1") (pintype "input"))
      (node (ref "R44") (pin "1") (pinfunction "1_1") (pintype "input"))
      (node (ref "R45") (pin "1") (pinfunction "1_1") (pintype "input"))
      (node (ref "SW7") (pin "3") (pinfunction "3_3") (pintype "unspecified"))
      (node (ref "SW7") (pin "4") (pinfunction "4_4") (pintype "unspecified"))
      (node (ref "SW9") (pin "3") (pinfunction "3_3") (pintype "unspecified"))
      (node (ref "SW9") (pin "4") (pinfunction "4_4") (pintype "unspecified"))
      (node (ref "U1") (pin "1") (pinfunction "GND_1") (pintype "unspecified"))
      (node (ref "U1") (pin "15") (pinfunction "GND_15") (pintype "unspecified"))
      (node (ref "U1") (pin "38") (pinfunction "GND_38") (pintype "unspecified"))
      (node (ref "U1") (pin "39") (pinfunction "GND_39") (pintype "unspecified"))
      (node (ref "U2") (pin "29") (pinfunction "EP_29") (pintype "unspecified"))
      (node (ref "U2") (pin "3") (pinfunction "GND_3") (pintype "unspecified"))
      (node (ref "U5") (pin "1") (pinfunction "GND_1") (pintype "input"))
      (node (ref "U6") (pin "11") (pinfunction "EP_11") (pintype "unspecified"))
      (node (ref "U6") (pin "3") (pinfunction "PGND_3") (pintype "unspecified"))
      (node (ref "U6") (pin "9") (pinfunction "GND_9") (pintype "unspecified"))
      (node (ref "U7") (pin "1") (pinfunction "1OE_1") (pintype "input"))
      (node (ref "U7") (pin "10") (pinfunction "3OE_10") (pintype "input"))
      (node (ref "U7") (pin "13") (pinfunction "4OE_13") (pintype "input"))
      (node (ref "U7") (pin "4") (pinfunction "2OE_4") (pintype "input"))
      (node (ref "U7") (pin "7") (pinfunction "GND_7") (pintype "input"))
      (node (ref "U8") (pin "2") (pinfunction "2_2") (pintype "input"))
      (node (ref "U9") (pin "2") (pinfunction "2_2") (pintype "input"))
      (node (ref "USB1") (pin "10") (pinfunction "EP_10") (pintype "input"))
      (node (ref "USB1") (pin "5") (pinfunction "GND_5") (pintype "input"))
      (node (ref "USB1") (pin "6") (pinfunction "EP_6") (pintype "input"))
      (node (ref "USB1") (pin "7") (pinfunction "EP_7") (pintype "input"))
      (node (ref "USB1") (pin "8") (pinfunction "EP_8") (pintype "input"))
      (node (ref "USB1") (pin "9") (pinfunction "EP_9") (pintype "input"))
    )
    (net (code "44") (name "Net-(CARD3-DAT0)") (class "Default")
      (node (ref "CARD3") (pin "7") (pinfunction "DAT0_7") (pintype "input"))
      (node (ref "R33") (pin "2") (pinfunction "2_2") (pintype "input"))
    )
    (net (code "45") (name "Net-(D7-K)") (class "Default")
      (node (ref "D7") (pin "1") (pinfunction "K_1") (pintype "unspecified"))
      (node (ref "R38") (pin "2") (pinfunction "2_2") (pintype "input"))
      (node (ref "U11") (pin "2") (pinfunction "2_2") (pintype "unspecified"))
    )
    (net (code "46") (name "Net-(D8-K)") (class "Default")
      (node (ref "D8") (pin "1") (pinfunction "K_1") (pintype "unspecified"))
      (node (ref "R39") (pin "2") (pinfunction "2_2") (pintype "input"))
      (node (ref "U10") (pin "2") (pinfunction "2_2") (pintype "unspecified"))
    )
    (net (code "47") (name "Net-(Q2-B)") (class "Default")
      (node (ref "Q2") (pin "1") (pinfunction "B_1") (pintype "input"))
      (node (ref "R28") (pin "2") (pinfunction "2_2") (pintype "input"))
    )
    (net (code "48") (name "Net-(Q3-B)") (class "Default")
      (node (ref "Q3") (pin "1") (pinfunction "B_1") (pintype "input"))
      (node (ref "R29") (pin "2") (pinfunction "2_2") (pintype "input"))
    )
    (net (code "49") (name "Net-(Q4-B)") (class "Default")
      (node (ref "Q4") (pin "2") (pinfunction "B_2") (pintype "input"))
      (node (ref "R47") (pin "2") (pinfunction "2_2") (pintype "input"))
    )
    (net (code "50") (name "Net-(Q4-C)") (class "Default")
      (node (ref "Q4") (pin "3") (pinfunction "C_3") (pintype "input"))
      (node (ref "Q5") (pin "1") (pinfunction "G_1") (pintype "unspecified"))
      (node (ref "R46") (pin "1") (pinfunction "1_1") (pintype "unspecified"))
    )
    (net (code "51") (name "Net-(R41-Pad2)") (class "Default")
      (node (ref "R41") (pin "2") (pinfunction "2_2") (pintype "input"))
      (node (ref "U11") (pin "1") (pinfunction "1_1") (pintype "unspecified"))
    )
    (net (code "52") (name "Net-(R43-Pad2)") (class "Default")
      (node (ref "R43") (pin "2") (pinfunction "2_2") (pintype "input"))
      (node (ref "U10") (pin "1") (pinfunction "1_1") (pintype "unspecified"))
    )
    (net (code "53") (name "Net-(U2-TXD)") (class "Default")
      (node (ref "R32") (pin "1") (pinfunction "1_1") (pintype "input"))
      (node (ref "U2") (pin "26") (pinfunction "TXD_26") (pintype "unspecified"))
    )
    (net (code "54") (name "Net-(U2-VDD)") (class "Default")
      (node (ref "C29") (pin "2") (pinfunction "2_2") (pintype "unspecified"))
      (node (ref "U2") (pin "6") (pinfunction "VDD_6") (pintype "unspecified"))
    )
    (net (code "55") (name "Net-(U5-DISCH)") (class "Default")
      (node (ref "D5") (pin "2") (pinfunction "2_2") (pintype "unspecified"))
      (node (ref "NTC_1") (pin "2") (pinfunction "2_2") (pintype "unspecified"))
      (node (ref "NTC_2") (pin "1") (pinfunction "1_1") (pintype "unspecified"))
      (node (ref "U5") (pin "7") (pinfunction "DISCH_7") (pintype "input"))
    )
    (net (code "56") (name "Net-(U5-THRES)") (class "Default")
      (node (ref "C30") (pin "2") (pinfunction "2_2") (pintype "input"))
      (node (ref "D5") (pin "1") (pinfunction "1_1") (pintype "unspecified"))
      (node (ref "NTC_2") (pin "2") (pinfunction "2_2") (pintype "unspecified"))
      (node (ref "U5") (pin "2") (pinfunction "TRIG_2") (pintype "input"))
      (node (ref "U5") (pin "6") (pinfunction "THRES_6") (pintype "input"))
    )
    (net (code "57") (name "Net-(U6-L1)") (class "Default")
      (node (ref "L2") (pin "2") (pinfunction "2_2") (pintype "unspecified"))
      (node (ref "U6") (pin "4") (pinfunction "L1_4") (pintype "unspecified"))
    )
    (net (code "58") (name "Net-(U6-L2)") (class "Default")
      (node (ref "L2") (pin "1") (pinfunction "1_1") (pintype "unspecified"))
      (node (ref "U6") (pin "2") (pinfunction "L2_2") (pintype "unspecified"))
    )
    (net (code "59") (name "Net-(U6-VINA)") (class "Default")
      (node (ref "C21") (pin "2") (pinfunction "2_2") (pintype "unspecified"))
      (node (ref "R27") (pin "1") (pinfunction "1_1") (pintype "input"))
      (node (ref "U6") (pin "8") (pinfunction "VINA_8") (pintype "unspecified"))
    )
    (net (code "60") (name "Net-(U7-1A)") (class "Default")
      (node (ref "R34") (pin "2") (pinfunction "2_2") (pintype "input"))
      (node (ref "U7") (pin "2") (pinfunction "1A_2") (pintype "input"))
    )
    (net (code "61") (name "Net-(U7-2A)") (class "Default")
      (node (ref "R35") (pin "2") (pinfunction "2_2") (pintype "input"))
      (node (ref "U7") (pin "5") (pinfunction "2A_5") (pintype "input"))
    )
    (net (code "62") (name "Net-(U7-3A)") (class "Default")
      (node (ref "R36") (pin "1") (pinfunction "1_1") (pintype "input"))
      (node (ref "U7") (pin "9") (pinfunction "3A_9") (pintype "input"))
    )
    (net (code "63") (name "Net-(U12-Pad2)") (class "Default")
      (node (ref "U12") (pin "2") (pinfunction "2_2") (pintype "unspecified"))
      (node (ref "U8") (pin "1") (pinfunction "1_1") (pintype "input"))
      (node (ref "U9") (pin "1") (pinfunction "1_1") (pintype "input"))
    )
    (net (code "64") (name "Net-(USB1-VCC)") (class "Default")
      (node (ref "C25") (pin "2") (pinfunction "2_2") (pintype "unspecified"))
      (node (ref "D1") (pin "2") (pinfunction "2_2") (pintype "unspecified"))
      (node (ref "D2") (pin "2") (pinfunction "2_2") (pintype "input"))
      (node (ref "USB1") (pin "1") (pinfunction "VCC_1") (pintype "input"))
    )
    (net (code "65") (name "VCC_555") (class "Default")
      (node (ref "NTC_1") (pin "1") (pinfunction "1_1") (pintype "unspecified"))
      (node (ref "Q5") (pin "2") (pinfunction "D_2") (pintype "unspecified"))
      (node (ref "R45") (pin "2") (pinfunction "2_2") (pintype "input"))
      (node (ref "U5") (pin "4") (pinfunction "RESET_4") (pintype "input"))
      (node (ref "U5") (pin "8") (pinfunction "VCC_8") (pintype "input"))
    )
    (net (code "66") (name "VCC_BATTERY") (class "Default")
      (node (ref "C24") (pin "2") (pinfunction "2_2") (pintype "input"))
      (node (ref "Q5") (pin "3") (pinfunction "S_3") (pintype "unspecified"))
      (node (ref "R27") (pin "2") (pinfunction "2_2") (pintype "input"))
      (node (ref "R38") (pin "1") (pinfunction "1_1") (pintype "input"))
      (node (ref "R39") (pin "1") (pinfunction "1_1") (pintype "input"))
      (node (ref "R46") (pin "2") (pinfunction "2_2") (pintype "unspecified"))
      (node (ref "U12") (pin "1") (pinfunction "1_1") (pintype "unspecified"))
      (node (ref "U6") (pin "5") (pinfunction "VIN_5") (pintype "unspecified"))
    )
    (net (code "67") (name "unconnected-(CARD3-CD-Pad9)") (class "Default")
      (node (ref "CARD3") (pin "9") (pinfunction "CD_9") (pintype "input+no_connect"))
    )
    (net (code "68") (name "unconnected-(CARD3-DAT1-Pad8)") (class "Default")
      (node (ref "CARD3") (pin "8") (pinfunction "DAT1_8") (pintype "input+no_connect"))
    )
    (net (code "69") (name "unconnected-(CARD3-DAT2-Pad1)") (class "Default")
      (node (ref "CARD3") (pin "1") (pinfunction "DAT2_1") (pintype "input+no_connect"))
    )
    (net (code "70") (name "unconnected-(H1-Pad6)") (class "Default")
      (node (ref "H1") (pin "6") (pinfunction "6_6") (pintype "unspecified+no_connect"))
    )
    (net (code "71") (name "unconnected-(H1-Pad7)") (class "Default")
      (node (ref "H1") (pin "7") (pinfunction "7_7") (pintype "unspecified+no_connect"))
    )
    (net (code "72") (name "unconnected-(H1-Pad9)") (class "Default")
      (node (ref "H1") (pin "9") (pinfunction "9_9") (pintype "unspecified+no_connect"))
    )
    (net (code "73") (name "unconnected-(H1-Pad10)") (class "Default")
      (node (ref "H1") (pin "10") (pinfunction "10_10") (pintype "unspecified+no_connect"))
    )
    (net (code "74") (name "unconnected-(H2-Pad3)") (class "Default")
      (node (ref "H2") (pin "3") (pinfunction "3_3") (pintype "unspecified+no_connect"))
    )
    (net (code "75") (name "unconnected-(H2-Pad5)") (class "Default")
      (node (ref "H2") (pin "5") (pinfunction "5_5") (pintype "unspecified+no_connect"))
    )
    (net (code "76") (name "unconnected-(H2-Pad6)") (class "Default")
      (node (ref "H2") (pin "6") (pinfunction "6_6") (pintype "unspecified+no_connect"))
    )
    (net (code "77") (name "unconnected-(H2-Pad9)") (class "Default")
      (node (ref "H2") (pin "9") (pinfunction "9_9") (pintype "unspecified+no_connect"))
    )
    (net (code "78") (name "unconnected-(H2-Pad10)") (class "Default")
      (node (ref "H2") (pin "10") (pinfunction "10_10") (pintype "unspecified+no_connect"))
    )
    (net (code "79") (name "unconnected-(H2-Pad11)") (class "Default")
      (node (ref "H2") (pin "11") (pinfunction "11_11") (pintype "unspecified+no_connect"))
    )
    (net (code "80") (name "unconnected-(U1-NC-Pad17)") (class "Default")
      (node (ref "U1") (pin "17") (pinfunction "NC_17") (pintype "unspecified+no_connect"))
    )
    (net (code "81") (name "unconnected-(U1-NC-Pad18)") (class "Default")
      (node (ref "U1") (pin "18") (pinfunction "NC_18") (pintype "unspecified+no_connect"))
    )
    (net (code "82") (name "unconnected-(U1-NC-Pad19)") (class "Default")
      (node (ref "U1") (pin "19") (pinfunction "NC_19") (pintype "unspecified+no_connect"))
    )
    (net (code "83") (name "unconnected-(U1-NC-Pad20)") (class "Default")
      (node (ref "U1") (pin "20") (pinfunction "NC_20") (pintype "unspecified+no_connect"))
    )
    (net (code "84") (name "unconnected-(U1-NC-Pad21)") (class "Default")
      (node (ref "U1") (pin "21") (pinfunction "NC_21") (pintype "unspecified+no_connect"))
    )
    (net (code "85") (name "unconnected-(U1-NC-Pad22)") (class "Default")
      (node (ref "U1") (pin "22") (pinfunction "NC_22") (pintype "unspecified+no_connect"))
    )
    (net (code "86") (name "unconnected-(U1-NC-Pad32)") (class "Default")
      (node (ref "U1") (pin "32") (pinfunction "NC_32") (pintype "unspecified+no_connect"))
    )
    (net (code "87") (name "unconnected-(U2-CHR0-Pad15)") (class "Default")
      (node (ref "U2") (pin "15") (pinfunction "CHR0_15") (pintype "unspecified+no_connect"))
    )
    (net (code "88") (name "unconnected-(U2-CHR1-Pad14)") (class "Default")
      (node (ref "U2") (pin "14") (pinfunction "CHR1_14") (pintype "unspecified+no_connect"))
    )
    (net (code "89") (name "unconnected-(U2-CHREN-Pad13)") (class "Default")
      (node (ref "U2") (pin "13") (pinfunction "CHREN_13") (pintype "unspecified+no_connect"))
    )
    (net (code "90") (name "unconnected-(U2-CTS-Pad23)") (class "Default")
      (node (ref "U2") (pin "23") (pinfunction "CTS_23") (pintype "unspecified+no_connect"))
    )
    (net (code "91") (name "unconnected-(U2-DCD-Pad1)") (class "Default")
      (node (ref "U2") (pin "1") (pinfunction "DCD_1") (pintype "unspecified+no_connect"))
    )
    (net (code "92") (name "unconnected-(U2-DSR-Pad27)") (class "Default")
      (node (ref "U2") (pin "27") (pinfunction "DSR_27") (pintype "unspecified+no_connect"))
    )
    (net (code "93") (name "unconnected-(U2-GPIO.0{slash}TXT-Pad19)") (class "Default")
      (node (ref "U2") (pin "19") (pinfunction "GPIO.0/TXT_19") (pintype "unspecified+no_connect"))
    )
    (net (code "94") (name "unconnected-(U2-GPIO.1{slash}RXT-Pad18)") (class "Default")
      (node (ref "U2") (pin "18") (pinfunction "GPIO.1/RXT_18") (pintype "unspecified+no_connect"))
    )
    (net (code "95") (name "unconnected-(U2-GPIO.2{slash}RS485-Pad17)") (class "Default")
      (node (ref "U2") (pin "17") (pinfunction "GPIO.2/RS485_17") (pintype "unspecified+no_connect"))
    )
    (net (code "96") (name "unconnected-(U2-GPIO.3{slash}WAKEUP-Pad16)") (class "Default")
      (node (ref "U2") (pin "16") (pinfunction "GPIO.3/WAKEUP_16") (pintype "unspecified+no_connect"))
    )
    (net (code "97") (name "unconnected-(U2-GPIO.4-Pad22)") (class "Default")
      (node (ref "U2") (pin "22") (pinfunction "GPIO.4_22") (pintype "unspecified+no_connect"))
    )
    (net (code "98") (name "unconnected-(U2-GPIO.5-Pad21)") (class "Default")
      (node (ref "U2") (pin "21") (pinfunction "GPIO.5_21") (pintype "unspecified+no_connect"))
    )
    (net (code "99") (name "unconnected-(U2-GPIO.6-Pad20)") (class "Default")
      (node (ref "U2") (pin "20") (pinfunction "GPIO.6_20") (pintype "unspecified+no_connect"))
    )
    (net (code "100") (name "unconnected-(U2-NC-Pad10)") (class "Default")
      (node (ref "U2") (pin "10") (pinfunction "NC_10") (pintype "unspecified+no_connect"))
    )
    (net (code "101") (name "unconnected-(U2-RI{slash}CLK-Pad2)") (class "Default")
      (node (ref "U2") (pin "2") (pinfunction "RI/CLK_2") (pintype "unspecified+no_connect"))
    )
    (net (code "102") (name "unconnected-(U2-RSTb-Pad9)") (class "Default")
      (node (ref "U2") (pin "9") (pinfunction "RSTb_9") (pintype "unspecified"))
    )
    (net (code "103") (name "unconnected-(U2-SUSPEND-Pad12)") (class "Default")
      (node (ref "U2") (pin "12") (pinfunction "SUSPEND_12") (pintype "unspecified+no_connect"))
    )
    (net (code "104") (name "unconnected-(U2-SUSPENDb-Pad11)") (class "Default")
      (node (ref "U2") (pin "11") (pinfunction "SUSPENDb_11") (pintype "unspecified"))
    )
    (net (code "105") (name "unconnected-(U5-CONT-Pad5)") (class "Default")
      (node (ref "U5") (pin "5") (pinfunction "CONT_5") (pintype "input"))
    )
    (net (code "106") (name "unconnected-(U6-EN-Pad6)") (class "Default")
      (node (ref "U6") (pin "6") (pinfunction "EN_6") (pintype "unspecified"))
    )
    (net (code "107") (name "unconnected-(U6-PS{slash}SYNC-Pad7)") (class "Default")
      (node (ref "U6") (pin "7") (pinfunction "PS/SYNC_7") (pintype "unspecified"))
    )
    (net (code "108") (name "unconnected-(U12-Pad3)") (class "Default")
      (node (ref "U12") (pin "3") (pinfunction "3_3") (pintype "unspecified"))
    )
    (net (code "109") (name "unconnected-(USB1-ID-Pad4)") (class "Default")
      (node (ref "USB1") (pin "4") (pinfunction "ID_4") (pintype "input+no_connect"))
    )
  )
)
